# secondary_decoupling.net
KiCad netlist of a schematic drawn in Altium Designer
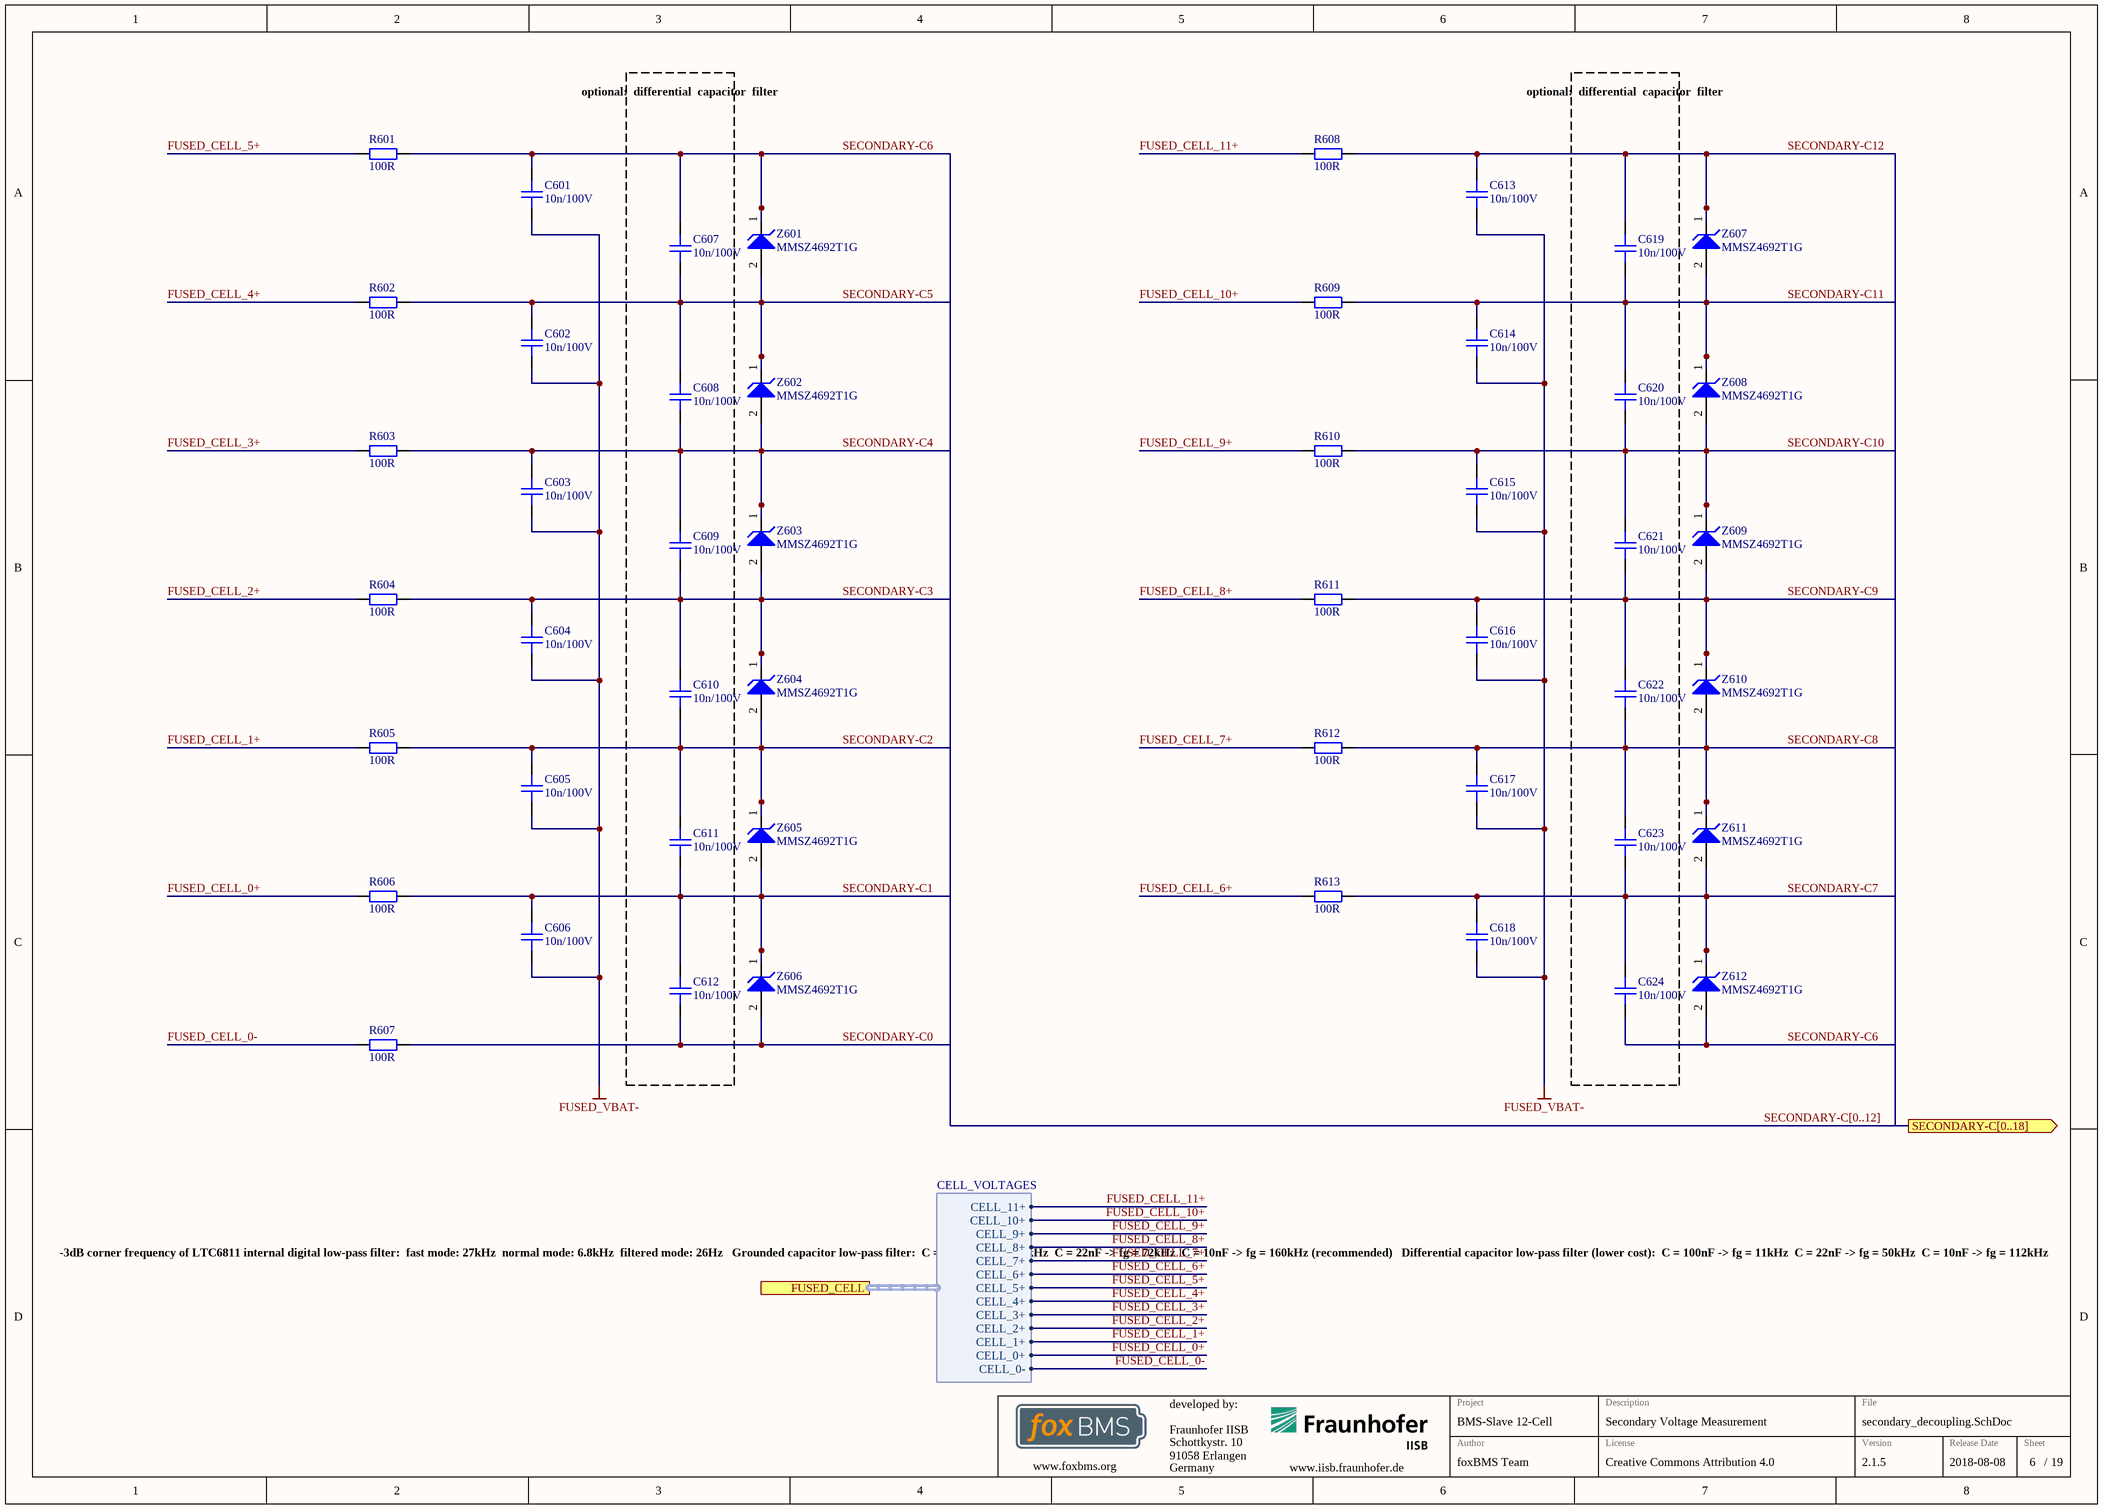
[diagram p0: secondary_decoupling.SchDoc]

(export (version "E")
  (design (tool "Eeschema 10.0.6"))
  (components
    (comp (ref "C601")
      (value "10n/100V")
      (footprint "CAPC1608X08N")
      (description "MLCC")
      (fields (field (name "PART NUMBER") "gen_C_ceramic_10n_100V_X7R_0603"))
      (libsource (lib "OE750") (part "C"))
    )
    (comp (ref "C602")
      (value "10n/100V")
      (footprint "CAPC1608X08N")
      (description "MLCC")
      (fields (field (name "PART NUMBER") "gen_C_ceramic_10n_100V_X7R_0603"))
      (libsource (lib "OE750") (part "C"))
    )
    (comp (ref "C603")
      (value "10n/100V")
      (footprint "CAPC1608X08N")
      (description "MLCC")
      (fields (field (name "PART NUMBER") "gen_C_ceramic_10n_100V_X7R_0603"))
      (libsource (lib "OE750") (part "C"))
    )
    (comp (ref "C604")
      (value "10n/100V")
      (footprint "CAPC1608X08N")
      (description "MLCC")
      (fields (field (name "PART NUMBER") "gen_C_ceramic_10n_100V_X7R_0603"))
      (libsource (lib "OE750") (part "C"))
    )
    (comp (ref "C605")
      (value "10n/100V")
      (footprint "CAPC1608X08N")
      (description "MLCC")
      (fields (field (name "PART NUMBER") "gen_C_ceramic_10n_100V_X7R_0603"))
      (libsource (lib "OE750") (part "C"))
    )
    (comp (ref "C606")
      (value "10n/100V")
      (footprint "CAPC1608X08N")
      (description "MLCC")
      (fields (field (name "PART NUMBER") "gen_C_ceramic_10n_100V_X7R_0603"))
      (libsource (lib "OE750") (part "C"))
    )
    (comp (ref "C607")
      (value "10n/100V")
      (footprint "CAPC1608X08N")
      (description "MLCC")
      (fields (field (name "PART NUMBER") "gen_C_ceramic_10n_100V_X7R_0603"))
      (libsource (lib "OE750") (part "C"))
    )
    (comp (ref "C608")
      (value "10n/100V")
      (footprint "CAPC1608X08N")
      (description "MLCC")
      (fields (field (name "PART NUMBER") "gen_C_ceramic_10n_100V_X7R_0603"))
      (libsource (lib "OE750") (part "C"))
    )
    (comp (ref "C609")
      (value "10n/100V")
      (footprint "CAPC1608X08N")
      (description "MLCC")
      (fields (field (name "PART NUMBER") "gen_C_ceramic_10n_100V_X7R_0603"))
      (libsource (lib "OE750") (part "C"))
    )
    (comp (ref "C610")
      (value "10n/100V")
      (footprint "CAPC1608X08N")
      (description "MLCC")
      (fields (field (name "PART NUMBER") "gen_C_ceramic_10n_100V_X7R_0603"))
      (libsource (lib "OE750") (part "C"))
    )
    (comp (ref "C611")
      (value "10n/100V")
      (footprint "CAPC1608X08N")
      (description "MLCC")
      (fields (field (name "PART NUMBER") "gen_C_ceramic_10n_100V_X7R_0603"))
      (libsource (lib "OE750") (part "C"))
    )
    (comp (ref "C612")
      (value "10n/100V")
      (footprint "CAPC1608X08N")
      (description "MLCC")
      (fields (field (name "PART NUMBER") "gen_C_ceramic_10n_100V_X7R_0603"))
      (libsource (lib "OE750") (part "C"))
    )
    (comp (ref "C613")
      (value "10n/100V")
      (footprint "CAPC1608X08N")
      (description "MLCC")
      (fields (field (name "PART NUMBER") "gen_C_ceramic_10n_100V_X7R_0603"))
      (libsource (lib "OE750") (part "C"))
    )
    (comp (ref "C614")
      (value "10n/100V")
      (footprint "CAPC1608X08N")
      (description "MLCC")
      (fields (field (name "PART NUMBER") "gen_C_ceramic_10n_100V_X7R_0603"))
      (libsource (lib "OE750") (part "C"))
    )
    (comp (ref "C615")
      (value "10n/100V")
      (footprint "CAPC1608X08N")
      (description "MLCC")
      (fields (field (name "PART NUMBER") "gen_C_ceramic_10n_100V_X7R_0603"))
      (libsource (lib "OE750") (part "C"))
    )
    (comp (ref "C616")
      (value "10n/100V")
      (footprint "CAPC1608X08N")
      (description "MLCC")
      (fields (field (name "PART NUMBER") "gen_C_ceramic_10n_100V_X7R_0603"))
      (libsource (lib "OE750") (part "C"))
    )
    (comp (ref "C617")
      (value "10n/100V")
      (footprint "CAPC1608X08N")
      (description "MLCC")
      (fields (field (name "PART NUMBER") "gen_C_ceramic_10n_100V_X7R_0603"))
      (libsource (lib "OE750") (part "C"))
    )
    (comp (ref "C618")
      (value "10n/100V")
      (footprint "CAPC1608X08N")
      (description "MLCC")
      (fields (field (name "PART NUMBER") "gen_C_ceramic_10n_100V_X7R_0603"))
      (libsource (lib "OE750") (part "C"))
    )
    (comp (ref "C619")
      (value "10n/100V")
      (footprint "CAPC1608X08N")
      (description "MLCC")
      (fields (field (name "PART NUMBER") "gen_C_ceramic_10n_100V_X7R_0603"))
      (libsource (lib "OE750") (part "C"))
    )
    (comp (ref "C620")
      (value "10n/100V")
      (footprint "CAPC1608X08N")
      (description "MLCC")
      (fields (field (name "PART NUMBER") "gen_C_ceramic_10n_100V_X7R_0603"))
      (libsource (lib "OE750") (part "C"))
    )
    (comp (ref "C621")
      (value "10n/100V")
      (footprint "CAPC1608X08N")
      (description "MLCC")
      (fields (field (name "PART NUMBER") "gen_C_ceramic_10n_100V_X7R_0603"))
      (libsource (lib "OE750") (part "C"))
    )
    (comp (ref "C622")
      (value "10n/100V")
      (footprint "CAPC1608X08N")
      (description "MLCC")
      (fields (field (name "PART NUMBER") "gen_C_ceramic_10n_100V_X7R_0603"))
      (libsource (lib "OE750") (part "C"))
    )
    (comp (ref "C623")
      (value "10n/100V")
      (footprint "CAPC1608X08N")
      (description "MLCC")
      (fields (field (name "PART NUMBER") "gen_C_ceramic_10n_100V_X7R_0603"))
      (libsource (lib "OE750") (part "C"))
    )
    (comp (ref "C624")
      (value "10n/100V")
      (footprint "CAPC1608X08N")
      (description "MLCC")
      (fields (field (name "PART NUMBER") "gen_C_ceramic_10n_100V_X7R_0603"))
      (libsource (lib "OE750") (part "C"))
    )
    (comp (ref "R601")
      (value "100R")
      (footprint "RESC1608X05N")
      (description "SMD Resistor 100R 0603")
      (fields (field (name "PART NUMBER") "gen_R_100R_0603") (field (name "TOLERANCE") "1%"))
      (libsource (lib "OE750") (part "R"))
    )
    (comp (ref "R602")
      (value "100R")
      (footprint "RESC1608X05N")
      (description "SMD Resistor 100R 0603")
      (fields (field (name "PART NUMBER") "gen_R_100R_0603") (field (name "TOLERANCE") "1%"))
      (libsource (lib "OE750") (part "R"))
    )
    (comp (ref "R603")
      (value "100R")
      (footprint "RESC1608X05N")
      (description "SMD Resistor 100R 0603")
      (fields (field (name "PART NUMBER") "gen_R_100R_0603") (field (name "TOLERANCE") "1%"))
      (libsource (lib "OE750") (part "R"))
    )
    (comp (ref "R604")
      (value "100R")
      (footprint "RESC1608X05N")
      (description "SMD Resistor 100R 0603")
      (fields (field (name "PART NUMBER") "gen_R_100R_0603") (field (name "TOLERANCE") "1%"))
      (libsource (lib "OE750") (part "R"))
    )
    (comp (ref "R605")
      (value "100R")
      (footprint "RESC1608X05N")
      (description "SMD Resistor 100R 0603")
      (fields (field (name "PART NUMBER") "gen_R_100R_0603") (field (name "TOLERANCE") "1%"))
      (libsource (lib "OE750") (part "R"))
    )
    (comp (ref "R606")
      (value "100R")
      (footprint "RESC1608X05N")
      (description "SMD Resistor 100R 0603")
      (fields (field (name "PART NUMBER") "gen_R_100R_0603") (field (name "TOLERANCE") "1%"))
      (libsource (lib "OE750") (part "R"))
    )
    (comp (ref "R607")
      (value "100R")
      (footprint "RESC1608X05N")
      (description "SMD Resistor 100R 0603")
      (fields (field (name "PART NUMBER") "gen_R_100R_0603") (field (name "TOLERANCE") "1%"))
      (libsource (lib "OE750") (part "R"))
    )
    (comp (ref "R608")
      (value "100R")
      (footprint "RESC1608X05N")
      (description "SMD Resistor 100R 0603")
      (fields (field (name "PART NUMBER") "gen_R_100R_0603") (field (name "TOLERANCE") "1%"))
      (libsource (lib "OE750") (part "R"))
    )
    (comp (ref "R609")
      (value "100R")
      (footprint "RESC1608X05N")
      (description "SMD Resistor 100R 0603")
      (fields (field (name "PART NUMBER") "gen_R_100R_0603") (field (name "TOLERANCE") "1%"))
      (libsource (lib "OE750") (part "R"))
    )
    (comp (ref "R610")
      (value "100R")
      (footprint "RESC1608X05N")
      (description "SMD Resistor 100R 0603")
      (fields (field (name "PART NUMBER") "gen_R_100R_0603") (field (name "TOLERANCE") "1%"))
      (libsource (lib "OE750") (part "R"))
    )
    (comp (ref "R611")
      (value "100R")
      (footprint "RESC1608X05N")
      (description "SMD Resistor 100R 0603")
      (fields (field (name "PART NUMBER") "gen_R_100R_0603") (field (name "TOLERANCE") "1%"))
      (libsource (lib "OE750") (part "R"))
    )
    (comp (ref "R612")
      (value "100R")
      (footprint "RESC1608X05N")
      (description "SMD Resistor 100R 0603")
      (fields (field (name "PART NUMBER") "gen_R_100R_0603") (field (name "TOLERANCE") "1%"))
      (libsource (lib "OE750") (part "R"))
    )
    (comp (ref "R613")
      (value "100R")
      (footprint "RESC1608X05N")
      (description "SMD Resistor 100R 0603")
      (fields (field (name "PART NUMBER") "gen_R_100R_0603") (field (name "TOLERANCE") "1%"))
      (libsource (lib "OE750") (part "R"))
    )
    (comp (ref "Z601")
      (value "MMSZ4692T1G")
      (footprint "ONSC-SOD-123-2-425-04_V")
      (description "Zener Voltage Regulator, 500 mW, 2-Pin SOD-123, Pb-Free, Tape and Reel")
      (fields (field (name "MANUFACTURER") "On Semiconductor"))
      (libsource (lib "Altium Content Vault") (part "ONSC-K1A2-2"))
    )
    (comp (ref "Z602")
      (value "MMSZ4692T1G")
      (footprint "ONSC-SOD-123-2-425-04_V")
      (description "Zener Voltage Regulator, 500 mW, 2-Pin SOD-123, Pb-Free, Tape and Reel")
      (fields (field (name "MANUFACTURER") "On Semiconductor"))
      (libsource (lib "Altium Content Vault") (part "ONSC-K1A2-2"))
    )
    (comp (ref "Z603")
      (value "MMSZ4692T1G")
      (footprint "ONSC-SOD-123-2-425-04_V")
      (description "Zener Voltage Regulator, 500 mW, 2-Pin SOD-123, Pb-Free, Tape and Reel")
      (fields (field (name "MANUFACTURER") "On Semiconductor"))
      (libsource (lib "Altium Content Vault") (part "ONSC-K1A2-2"))
    )
    (comp (ref "Z604")
      (value "MMSZ4692T1G")
      (footprint "ONSC-SOD-123-2-425-04_V")
      (description "Zener Voltage Regulator, 500 mW, 2-Pin SOD-123, Pb-Free, Tape and Reel")
      (fields (field (name "MANUFACTURER") "On Semiconductor"))
      (libsource (lib "Altium Content Vault") (part "ONSC-K1A2-2"))
    )
    (comp (ref "Z605")
      (value "MMSZ4692T1G")
      (footprint "ONSC-SOD-123-2-425-04_V")
      (description "Zener Voltage Regulator, 500 mW, 2-Pin SOD-123, Pb-Free, Tape and Reel")
      (fields (field (name "MANUFACTURER") "On Semiconductor"))
      (libsource (lib "Altium Content Vault") (part "ONSC-K1A2-2"))
    )
    (comp (ref "Z606")
      (value "MMSZ4692T1G")
      (footprint "ONSC-SOD-123-2-425-04_V")
      (description "Zener Voltage Regulator, 500 mW, 2-Pin SOD-123, Pb-Free, Tape and Reel")
      (fields (field (name "MANUFACTURER") "On Semiconductor"))
      (libsource (lib "Altium Content Vault") (part "ONSC-K1A2-2"))
    )
    (comp (ref "Z607")
      (value "MMSZ4692T1G")
      (footprint "ONSC-SOD-123-2-425-04_V")
      (description "Zener Voltage Regulator, 500 mW, 2-Pin SOD-123, Pb-Free, Tape and Reel")
      (fields (field (name "MANUFACTURER") "On Semiconductor"))
      (libsource (lib "Altium Content Vault") (part "ONSC-K1A2-2"))
    )
    (comp (ref "Z608")
      (value "MMSZ4692T1G")
      (footprint "ONSC-SOD-123-2-425-04_V")
      (description "Zener Voltage Regulator, 500 mW, 2-Pin SOD-123, Pb-Free, Tape and Reel")
      (fields (field (name "MANUFACTURER") "On Semiconductor"))
      (libsource (lib "Altium Content Vault") (part "ONSC-K1A2-2"))
    )
    (comp (ref "Z609")
      (value "MMSZ4692T1G")
      (footprint "ONSC-SOD-123-2-425-04_V")
      (description "Zener Voltage Regulator, 500 mW, 2-Pin SOD-123, Pb-Free, Tape and Reel")
      (fields (field (name "MANUFACTURER") "On Semiconductor"))
      (libsource (lib "Altium Content Vault") (part "ONSC-K1A2-2"))
    )
    (comp (ref "Z610")
      (value "MMSZ4692T1G")
      (footprint "ONSC-SOD-123-2-425-04_V")
      (description "Zener Voltage Regulator, 500 mW, 2-Pin SOD-123, Pb-Free, Tape and Reel")
      (fields (field (name "MANUFACTURER") "On Semiconductor"))
      (libsource (lib "Altium Content Vault") (part "ONSC-K1A2-2"))
    )
    (comp (ref "Z611")
      (value "MMSZ4692T1G")
      (footprint "ONSC-SOD-123-2-425-04_V")
      (description "Zener Voltage Regulator, 500 mW, 2-Pin SOD-123, Pb-Free, Tape and Reel")
      (fields (field (name "MANUFACTURER") "On Semiconductor"))
      (libsource (lib "Altium Content Vault") (part "ONSC-K1A2-2"))
    )
    (comp (ref "Z612")
      (value "MMSZ4692T1G")
      (footprint "ONSC-SOD-123-2-425-04_V")
      (description "Zener Voltage Regulator, 500 mW, 2-Pin SOD-123, Pb-Free, Tape and Reel")
      (fields (field (name "MANUFACTURER") "On Semiconductor"))
      (libsource (lib "Altium Content Vault") (part "ONSC-K1A2-2"))
    )
  )
  (nets
    (net (code "2") (name "/FUSED_CELL_0+") (class "Default")
      (node (ref "R606") (pin "1") (pinfunction "1_1") (pintype "passive"))
    )
    (net (code "3") (name "/FUSED_CELL_0-") (class "Default")
      (node (ref "R607") (pin "1") (pinfunction "1_1") (pintype "passive"))
    )
    (net (code "4") (name "/FUSED_CELL_1+") (class "Default")
      (node (ref "R605") (pin "1") (pinfunction "1_1") (pintype "passive"))
    )
    (net (code "5") (name "/FUSED_CELL_2+") (class "Default")
      (node (ref "R604") (pin "1") (pinfunction "1_1") (pintype "passive"))
    )
    (net (code "6") (name "/FUSED_CELL_3+") (class "Default")
      (node (ref "R603") (pin "1") (pinfunction "1_1") (pintype "passive"))
    )
    (net (code "7") (name "/FUSED_CELL_4+") (class "Default")
      (node (ref "R602") (pin "1") (pinfunction "1_1") (pintype "passive"))
    )
    (net (code "8") (name "/FUSED_CELL_5+") (class "Default")
      (node (ref "R601") (pin "1") (pinfunction "1_1") (pintype "passive"))
    )
    (net (code "9") (name "/FUSED_CELL_6+") (class "Default")
      (node (ref "R613") (pin "1") (pinfunction "1_1") (pintype "passive"))
    )
    (net (code "10") (name "/FUSED_CELL_7+") (class "Default")
      (node (ref "R612") (pin "1") (pinfunction "1_1") (pintype "passive"))
    )
    (net (code "11") (name "/FUSED_CELL_8+") (class "Default")
      (node (ref "R611") (pin "1") (pinfunction "1_1") (pintype "passive"))
    )
    (net (code "12") (name "/FUSED_CELL_9+") (class "Default")
      (node (ref "R610") (pin "1") (pinfunction "1_1") (pintype "passive"))
    )
    (net (code "13") (name "/FUSED_CELL_10+") (class "Default")
      (node (ref "R609") (pin "1") (pinfunction "1_1") (pintype "passive"))
    )
    (net (code "14") (name "/FUSED_CELL_11+") (class "Default")
      (node (ref "R608") (pin "1") (pinfunction "1_1") (pintype "passive"))
    )
    (net (code "15") (name "/SECONDARY-C0") (class "Default")
      (node (ref "C612") (pin "2") (pinfunction "2_2") (pintype "passive"))
      (node (ref "R607") (pin "2") (pinfunction "2_2") (pintype "passive"))
      (node (ref "Z606") (pin "2") (pinfunction "A_2") (pintype "passive"))
    )
    (net (code "16") (name "/SECONDARY-C1") (class "Default")
      (node (ref "C606") (pin "1") (pinfunction "1_1") (pintype "passive"))
      (node (ref "C611") (pin "2") (pinfunction "2_2") (pintype "passive"))
      (node (ref "C612") (pin "1") (pinfunction "1_1") (pintype "passive"))
      (node (ref "R606") (pin "2") (pinfunction "2_2") (pintype "passive"))
      (node (ref "Z605") (pin "2") (pinfunction "A_2") (pintype "passive"))
      (node (ref "Z606") (pin "1") (pinfunction "K_1") (pintype "passive"))
    )
    (net (code "17") (name "/SECONDARY-C2") (class "Default")
      (node (ref "C605") (pin "1") (pinfunction "1_1") (pintype "passive"))
      (node (ref "C610") (pin "2") (pinfunction "2_2") (pintype "passive"))
      (node (ref "C611") (pin "1") (pinfunction "1_1") (pintype "passive"))
      (node (ref "R605") (pin "2") (pinfunction "2_2") (pintype "passive"))
      (node (ref "Z604") (pin "2") (pinfunction "A_2") (pintype "passive"))
      (node (ref "Z605") (pin "1") (pinfunction "K_1") (pintype "passive"))
    )
    (net (code "18") (name "/SECONDARY-C3") (class "Default")
      (node (ref "C604") (pin "1") (pinfunction "1_1") (pintype "passive"))
      (node (ref "C609") (pin "2") (pinfunction "2_2") (pintype "passive"))
      (node (ref "C610") (pin "1") (pinfunction "1_1") (pintype "passive"))
      (node (ref "R604") (pin "2") (pinfunction "2_2") (pintype "passive"))
      (node (ref "Z603") (pin "2") (pinfunction "A_2") (pintype "passive"))
      (node (ref "Z604") (pin "1") (pinfunction "K_1") (pintype "passive"))
    )
    (net (code "19") (name "/SECONDARY-C4") (class "Default")
      (node (ref "C603") (pin "1") (pinfunction "1_1") (pintype "passive"))
      (node (ref "C608") (pin "2") (pinfunction "2_2") (pintype "passive"))
      (node (ref "C609") (pin "1") (pinfunction "1_1") (pintype "passive"))
      (node (ref "R603") (pin "2") (pinfunction "2_2") (pintype "passive"))
      (node (ref "Z602") (pin "2") (pinfunction "A_2") (pintype "passive"))
      (node (ref "Z603") (pin "1") (pinfunction "K_1") (pintype "passive"))
    )
    (net (code "20") (name "/SECONDARY-C5") (class "Default")
      (node (ref "C602") (pin "1") (pinfunction "1_1") (pintype "passive"))
      (node (ref "C607") (pin "2") (pinfunction "2_2") (pintype "passive"))
      (node (ref "C608") (pin "1") (pinfunction "1_1") (pintype "passive"))
      (node (ref "R602") (pin "2") (pinfunction "2_2") (pintype "passive"))
      (node (ref "Z601") (pin "2") (pinfunction "A_2") (pintype "passive"))
      (node (ref "Z602") (pin "1") (pinfunction "K_1") (pintype "passive"))
    )
    (net (code "21") (name "/SECONDARY-C6") (class "Default")
      (node (ref "C601") (pin "1") (pinfunction "1_1") (pintype "passive"))
      (node (ref "C607") (pin "1") (pinfunction "1_1") (pintype "passive"))
      (node (ref "C624") (pin "2") (pinfunction "2_2") (pintype "passive"))
      (node (ref "R601") (pin "2") (pinfunction "2_2") (pintype "passive"))
      (node (ref "Z601") (pin "1") (pinfunction "K_1") (pintype "passive"))
      (node (ref "Z612") (pin "2") (pinfunction "A_2") (pintype "passive"))
    )
    (net (code "22") (name "/SECONDARY-C7") (class "Default")
      (node (ref "C618") (pin "1") (pinfunction "1_1") (pintype "passive"))
      (node (ref "C623") (pin "2") (pinfunction "2_2") (pintype "passive"))
      (node (ref "C624") (pin "1") (pinfunction "1_1") (pintype "passive"))
      (node (ref "R613") (pin "2") (pinfunction "2_2") (pintype "passive"))
      (node (ref "Z611") (pin "2") (pinfunction "A_2") (pintype "passive"))
      (node (ref "Z612") (pin "1") (pinfunction "K_1") (pintype "passive"))
    )
    (net (code "23") (name "/SECONDARY-C8") (class "Default")
      (node (ref "C617") (pin "1") (pinfunction "1_1") (pintype "passive"))
      (node (ref "C622") (pin "2") (pinfunction "2_2") (pintype "passive"))
      (node (ref "C623") (pin "1") (pinfunction "1_1") (pintype "passive"))
      (node (ref "R612") (pin "2") (pinfunction "2_2") (pintype "passive"))
      (node (ref "Z610") (pin "2") (pinfunction "A_2") (pintype "passive"))
      (node (ref "Z611") (pin "1") (pinfunction "K_1") (pintype "passive"))
    )
    (net (code "24") (name "/SECONDARY-C9") (class "Default")
      (node (ref "C616") (pin "1") (pinfunction "1_1") (pintype "passive"))
      (node (ref "C621") (pin "2") (pinfunction "2_2") (pintype "passive"))
      (node (ref "C622") (pin "1") (pinfunction "1_1") (pintype "passive"))
      (node (ref "R611") (pin "2") (pinfunction "2_2") (pintype "passive"))
      (node (ref "Z609") (pin "2") (pinfunction "A_2") (pintype "passive"))
      (node (ref "Z610") (pin "1") (pinfunction "K_1") (pintype "passive"))
    )
    (net (code "25") (name "/SECONDARY-C10") (class "Default")
      (node (ref "C615") (pin "1") (pinfunction "1_1") (pintype "passive"))
      (node (ref "C620") (pin "2") (pinfunction "2_2") (pintype "passive"))
      (node (ref "C621") (pin "1") (pinfunction "1_1") (pintype "passive"))
      (node (ref "R610") (pin "2") (pinfunction "2_2") (pintype "passive"))
      (node (ref "Z608") (pin "2") (pinfunction "A_2") (pintype "passive"))
      (node (ref "Z609") (pin "1") (pinfunction "K_1") (pintype "passive"))
    )
    (net (code "26") (name "/SECONDARY-C11") (class "Default")
      (node (ref "C614") (pin "1") (pinfunction "1_1") (pintype "passive"))
      (node (ref "C619") (pin "2") (pinfunction "2_2") (pintype "passive"))
      (node (ref "C620") (pin "1") (pinfunction "1_1") (pintype "passive"))
      (node (ref "R609") (pin "2") (pinfunction "2_2") (pintype "passive"))
      (node (ref "Z607") (pin "2") (pinfunction "A_2") (pintype "passive"))
      (node (ref "Z608") (pin "1") (pinfunction "K_1") (pintype "passive"))
    )
    (net (code "27") (name "/SECONDARY-C12") (class "Default")
      (node (ref "C613") (pin "1") (pinfunction "1_1") (pintype "passive"))
      (node (ref "C619") (pin "1") (pinfunction "1_1") (pintype "passive"))
      (node (ref "R608") (pin "2") (pinfunction "2_2") (pintype "passive"))
      (node (ref "Z607") (pin "1") (pinfunction "K_1") (pintype "passive"))
    )
    (net (code "30") (name "FUSED_VBAT-") (class "Default")
      (node (ref "C601") (pin "2") (pinfunction "2_2") (pintype "passive"))
      (node (ref "C602") (pin "2") (pinfunction "2_2") (pintype "passive"))
      (node (ref "C603") (pin "2") (pinfunction "2_2") (pintype "passive"))
      (node (ref "C604") (pin "2") (pinfunction "2_2") (pintype "passive"))
      (node (ref "C605") (pin "2") (pinfunction "2_2") (pintype "passive"))
      (node (ref "C606") (pin "2") (pinfunction "2_2") (pintype "passive"))
      (node (ref "C613") (pin "2") (pinfunction "2_2") (pintype "passive"))
      (node (ref "C614") (pin "2") (pinfunction "2_2") (pintype "passive"))
      (node (ref "C615") (pin "2") (pinfunction "2_2") (pintype "passive"))
      (node (ref "C616") (pin "2") (pinfunction "2_2") (pintype "passive"))
      (node (ref "C617") (pin "2") (pinfunction "2_2") (pintype "passive"))
      (node (ref "C618") (pin "2") (pinfunction "2_2") (pintype "passive"))
    )
  )
)
